# IOExpanderBoard.net
KiCad netlist of a schematic drawn in EAGLE
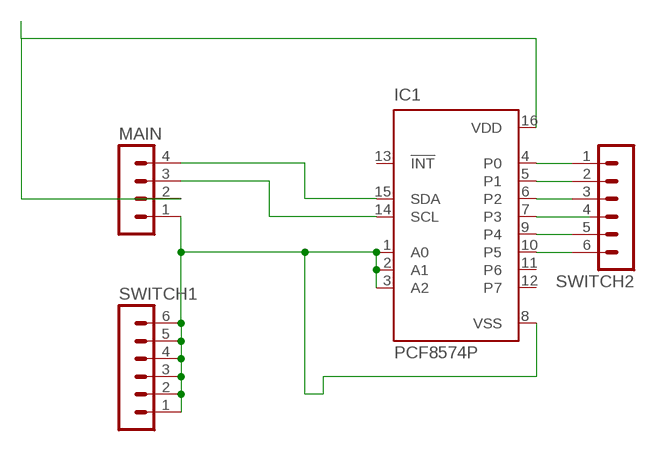
[diagram p0: schematic, sheet 1]

(export (version "E")
  (design (tool "Eeschema 10.0.6"))
  (components
    (comp (ref "IC1")
      (value "PCF8574P")
      (footprint "eagle-import:DIL16")
      (fields (field (name "MPN") "PCF8574PN"))
      (libsource (lib "eagle-import") (part "PCF8574P"))
    )
    (comp (ref "MAIN")
      (value "MA04-1")
      (footprint "eagle-import:MA04-1")
      (libsource (lib "eagle-import") (part "MA04-1"))
    )
    (comp (ref "SWITCH1")
      (value "MA06-1")
      (footprint "eagle-import:MA06-1")
      (libsource (lib "eagle-import") (part "MA06-1"))
    )
    (comp (ref "SWITCH2")
      (value "MA06-1")
      (footprint "eagle-import:MA06-1")
      (libsource (lib "eagle-import") (part "MA06-1"))
    )
  )
  (nets
    (net (code "1") (name "Net-(IC1-A0)") (class "Default")
      (node (ref "IC1") (pin "1") (pinfunction "A0_1") (pintype "input"))
      (node (ref "IC1") (pin "2") (pinfunction "A1_2") (pintype "input"))
      (node (ref "IC1") (pin "3") (pinfunction "A2_3") (pintype "input"))
      (node (ref "IC1") (pin "8") (pinfunction "VSS_8") (pintype "power_in"))
      (node (ref "MAIN") (pin "1") (pinfunction "1_1") (pintype "passive"))
      (node (ref "SWITCH1") (pin "1") (pinfunction "1_1") (pintype "passive"))
      (node (ref "SWITCH1") (pin "2") (pinfunction "2_2") (pintype "passive"))
      (node (ref "SWITCH1") (pin "3") (pinfunction "3_3") (pintype "passive"))
      (node (ref "SWITCH1") (pin "4") (pinfunction "4_4") (pintype "passive"))
      (node (ref "SWITCH1") (pin "5") (pinfunction "5_5") (pintype "passive"))
      (node (ref "SWITCH1") (pin "6") (pinfunction "6_6") (pintype "passive"))
    )
    (net (code "2") (name "Net-(IC1-P0)") (class "Default")
      (node (ref "IC1") (pin "4") (pinfunction "P0_4") (pintype "bidirectional"))
      (node (ref "SWITCH2") (pin "1") (pinfunction "1_1") (pintype "passive"))
    )
    (net (code "3") (name "Net-(IC1-P1)") (class "Default")
      (node (ref "IC1") (pin "5") (pinfunction "P1_5") (pintype "bidirectional"))
      (node (ref "SWITCH2") (pin "2") (pinfunction "2_2") (pintype "passive"))
    )
    (net (code "4") (name "Net-(IC1-P2)") (class "Default")
      (node (ref "IC1") (pin "6") (pinfunction "P2_6") (pintype "bidirectional"))
      (node (ref "SWITCH2") (pin "3") (pinfunction "3_3") (pintype "passive"))
    )
    (net (code "5") (name "Net-(IC1-P4)") (class "Default")
      (node (ref "IC1") (pin "9") (pinfunction "P4_9") (pintype "bidirectional"))
      (node (ref "SWITCH2") (pin "5") (pinfunction "5_5") (pintype "passive"))
    )
    (net (code "6") (name "Net-(IC1-P5)") (class "Default")
      (node (ref "IC1") (pin "10") (pinfunction "P5_10") (pintype "bidirectional"))
      (node (ref "SWITCH2") (pin "6") (pinfunction "6_6") (pintype "passive"))
    )
    (net (code "7") (name "Net-(IC1-SCL)") (class "Default")
      (node (ref "IC1") (pin "14") (pinfunction "SCL_14") (pintype "input"))
      (node (ref "MAIN") (pin "3") (pinfunction "3_3") (pintype "passive"))
    )
    (net (code "8") (name "Net-(IC1-SDA)") (class "Default")
      (node (ref "IC1") (pin "15") (pinfunction "SDA_15") (pintype "bidirectional"))
      (node (ref "MAIN") (pin "4") (pinfunction "4_4") (pintype "passive"))
    )
    (net (code "9") (name "Net-(IC1-VDD)") (class "Default")
      (node (ref "IC1") (pin "16") (pinfunction "VDD_16") (pintype "power_in"))
      (node (ref "MAIN") (pin "2") (pinfunction "2_2") (pintype "passive"))
    )
    (net (code "10") (name "unconnected-(IC1-P3-Pad7)") (class "Default")
      (node (ref "IC1") (pin "7") (pinfunction "P3_7") (pintype "bidirectional"))
    )
    (net (code "11") (name "unconnected-(IC1-P6-Pad11)") (class "Default")
      (node (ref "IC1") (pin "11") (pinfunction "P6_11") (pintype "bidirectional"))
    )
    (net (code "12") (name "unconnected-(IC1-P7-Pad12)") (class "Default")
      (node (ref "IC1") (pin "12") (pinfunction "P7_12") (pintype "bidirectional"))
    )
    (net (code "13") (name "unconnected-(IC1-~{INT}-Pad13)") (class "Default")
      (node (ref "IC1") (pin "13") (pinfunction "~{INT}_13") (pintype "output"))
    )
    (net (code "14") (name "unconnected-(SWITCH2-Pad4)") (class "Default")
      (node (ref "SWITCH2") (pin "4") (pinfunction "4_4") (pintype "passive"))
    )
  )
)
